# CR1000X_MUX.net
KiCad netlist of a schematic drawn in EAGLE
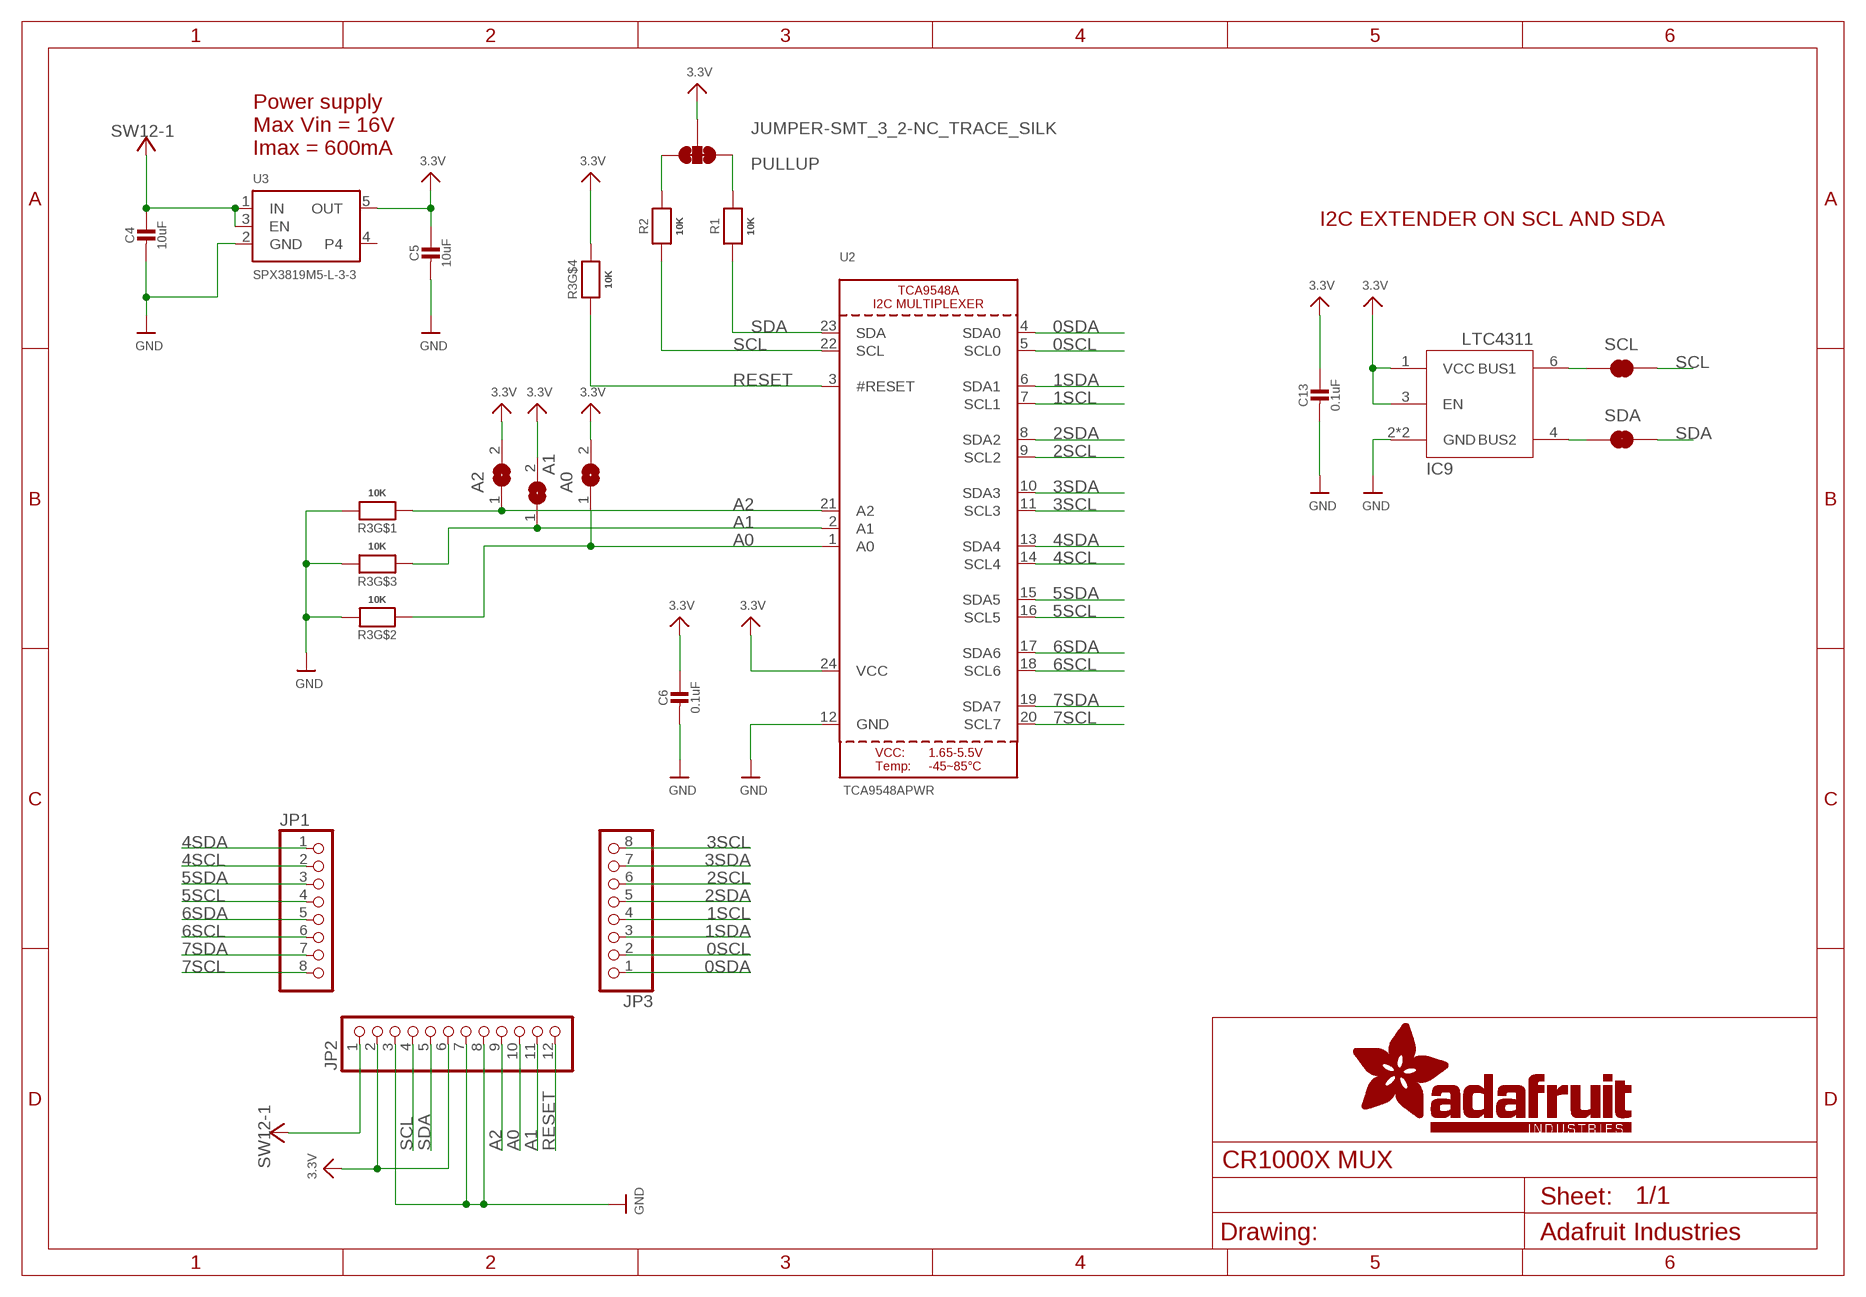
[diagram p0: schematic, sheet 1, part 1 of 2]
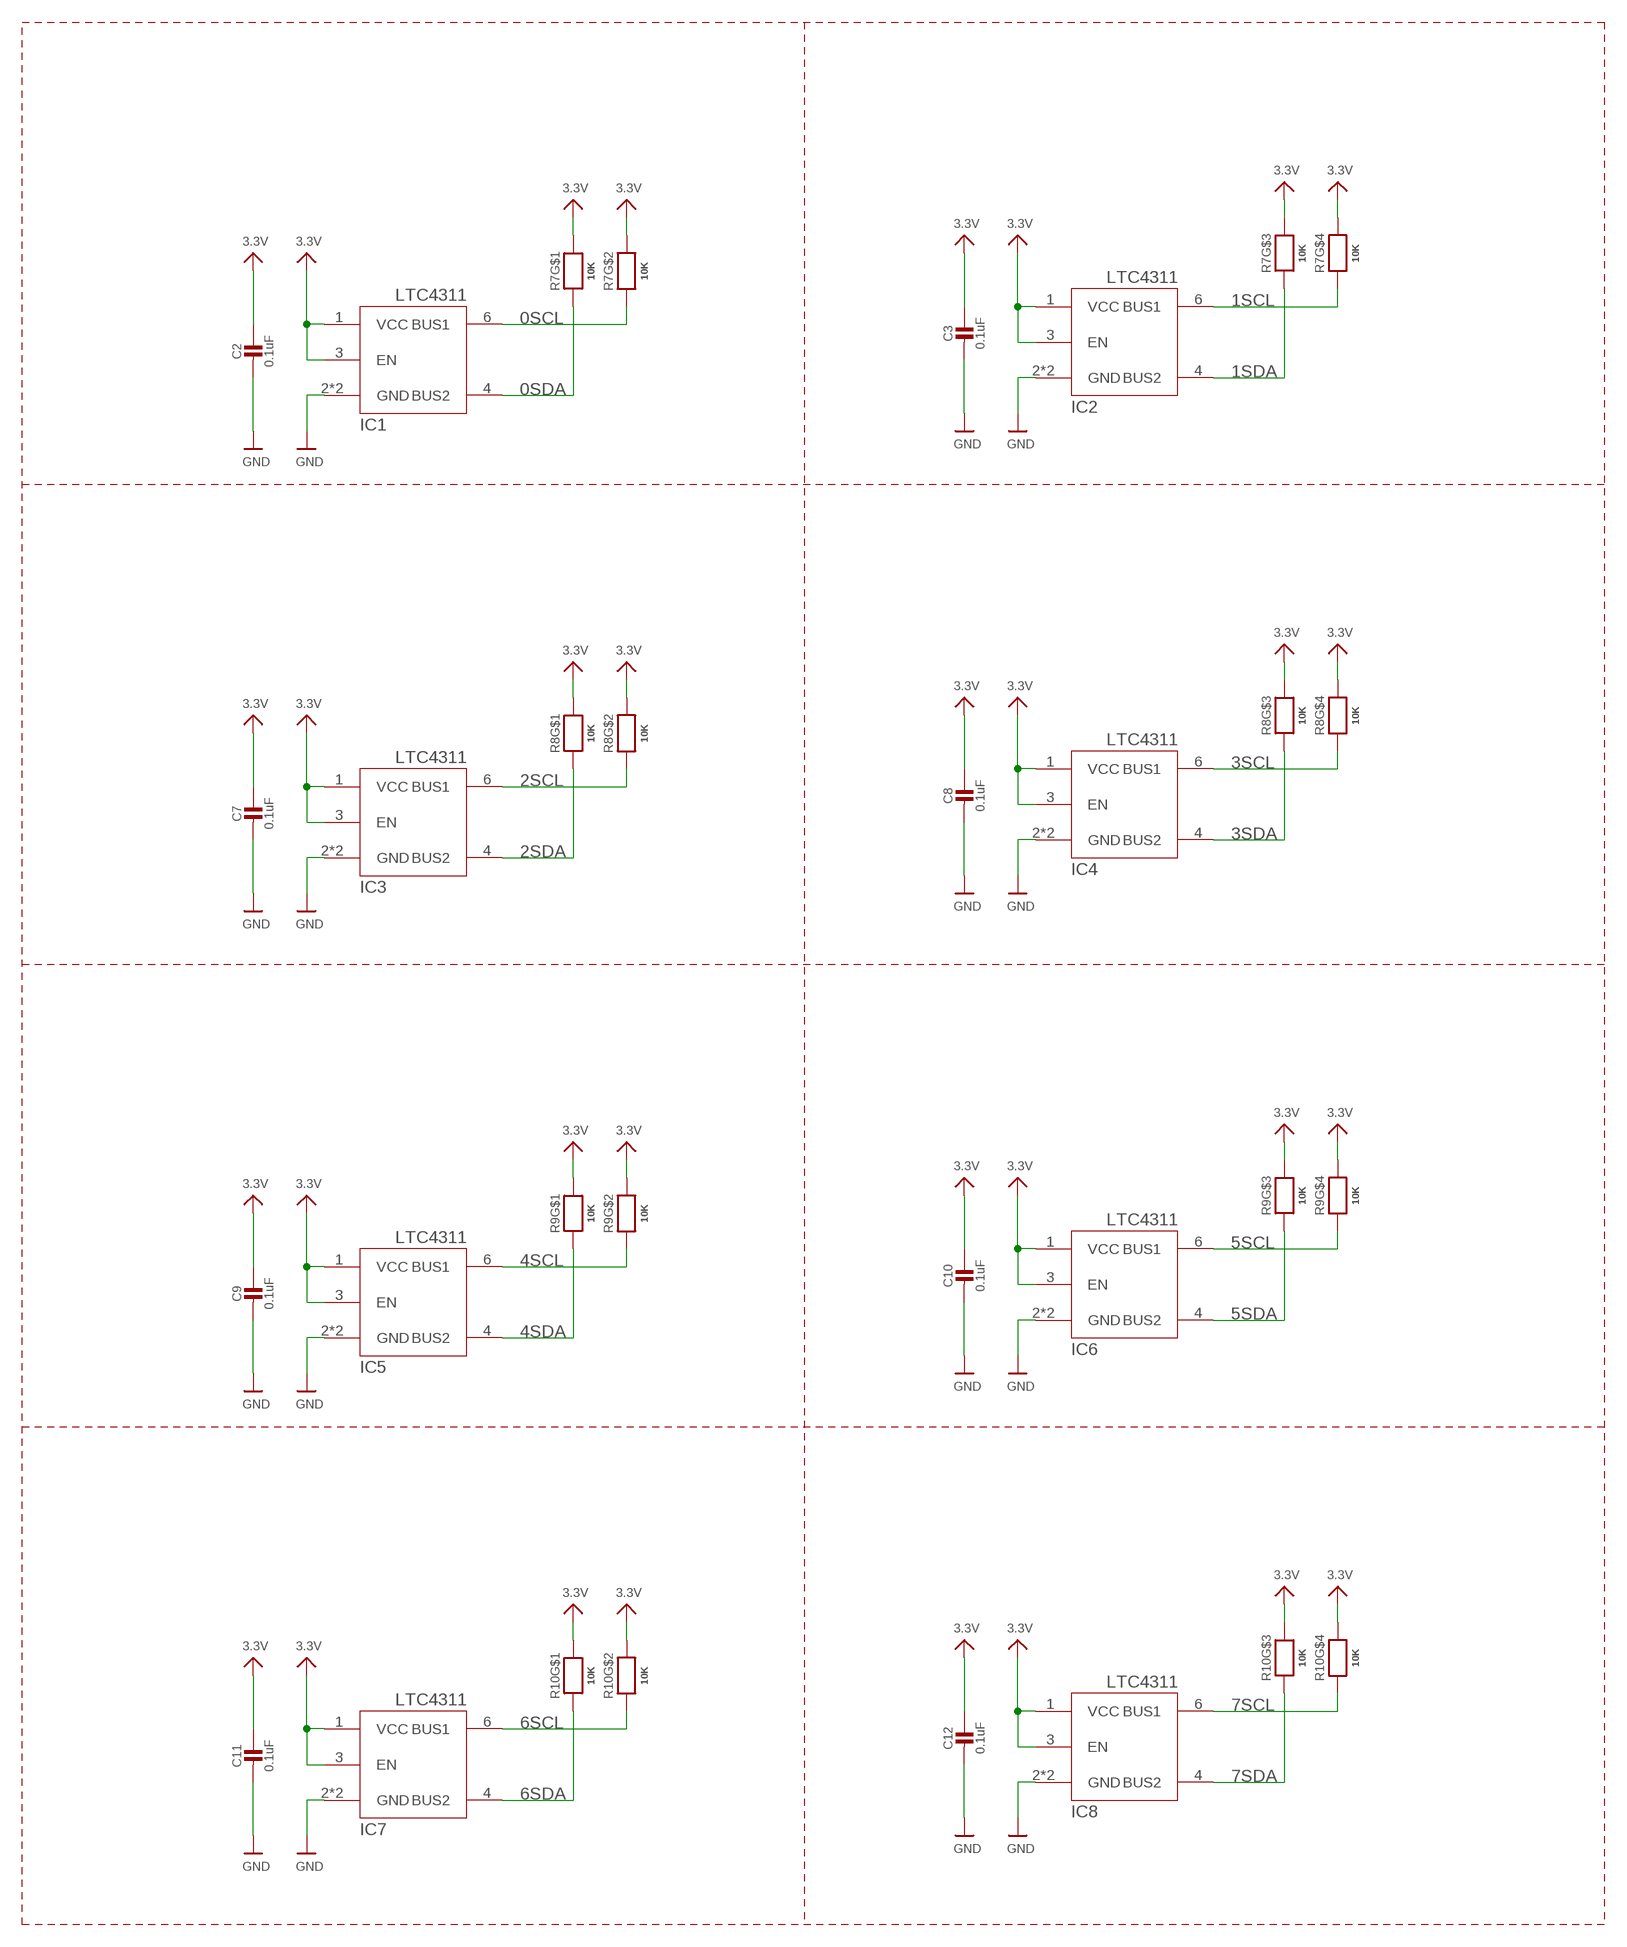
[diagram p1: schematic, sheet 1, part 2 of 2]

(export (version "E")
  (design (tool "Eeschema 10.0.6"))
  (components
    (comp (ref "A0")
      (value "SOLDERJUMPER")
      (footprint "eagle-import:SOLDERJUMPER_ARROW_NOPASTE")
      (libsource (lib "eagle-import") (part "SOLDERJUMPER"))
    )
    (comp (ref "A1")
      (value "SOLDERJUMPER")
      (footprint "eagle-import:SOLDERJUMPER_ARROW_NOPASTE")
      (libsource (lib "eagle-import") (part "SOLDERJUMPER"))
    )
    (comp (ref "A2")
      (value "SOLDERJUMPER")
      (footprint "eagle-import:SOLDERJUMPER_ARROW_NOPASTE")
      (libsource (lib "eagle-import") (part "SOLDERJUMPER"))
    )
    (comp (ref "C2")
      (value "0.1uF")
      (footprint "eagle-import:0603-NO")
      (libsource (lib "eagle-import") (part "CAP_CERAMIC0603_NO"))
    )
    (comp (ref "C3")
      (value "0.1uF")
      (footprint "eagle-import:0603-NO")
      (libsource (lib "eagle-import") (part "CAP_CERAMIC0603_NO"))
    )
    (comp (ref "C4")
      (value "10uF")
      (footprint "eagle-import:0805-NO")
      (libsource (lib "eagle-import") (part "CAP_CERAMIC0805-NOOUTLINE"))
    )
    (comp (ref "C5")
      (value "10uF")
      (footprint "eagle-import:0805-NO")
      (libsource (lib "eagle-import") (part "CAP_CERAMIC0805-NOOUTLINE"))
    )
    (comp (ref "C6")
      (value "0.1uF")
      (footprint "eagle-import:0603-NO")
      (libsource (lib "eagle-import") (part "CAP_CERAMIC0603_NO"))
    )
    (comp (ref "C7")
      (value "0.1uF")
      (footprint "eagle-import:0603-NO")
      (libsource (lib "eagle-import") (part "CAP_CERAMIC0603_NO"))
    )
    (comp (ref "C8")
      (value "0.1uF")
      (footprint "eagle-import:0603-NO")
      (libsource (lib "eagle-import") (part "CAP_CERAMIC0603_NO"))
    )
    (comp (ref "C9")
      (value "0.1uF")
      (footprint "eagle-import:0603-NO")
      (libsource (lib "eagle-import") (part "CAP_CERAMIC0603_NO"))
    )
    (comp (ref "C10")
      (value "0.1uF")
      (footprint "eagle-import:0603-NO")
      (libsource (lib "eagle-import") (part "CAP_CERAMIC0603_NO"))
    )
    (comp (ref "C11")
      (value "0.1uF")
      (footprint "eagle-import:0603-NO")
      (libsource (lib "eagle-import") (part "CAP_CERAMIC0603_NO"))
    )
    (comp (ref "C12")
      (value "0.1uF")
      (footprint "eagle-import:0603-NO")
      (libsource (lib "eagle-import") (part "CAP_CERAMIC0603_NO"))
    )
    (comp (ref "C13")
      (value "0.1uF")
      (footprint "eagle-import:0603-NO")
      (libsource (lib "eagle-import") (part "CAP_CERAMIC0603_NO"))
    )
    (comp (ref "IC1")
      (value "LTC4311_SC70")
      (footprint "eagle-import:SC70-6L")
      (libsource (lib "eagle-import") (part "LTC4311_SC70"))
    )
    (comp (ref "IC2")
      (value "LTC4311_SC70")
      (footprint "eagle-import:SC70-6L")
      (libsource (lib "eagle-import") (part "LTC4311_SC70"))
    )
    (comp (ref "IC3")
      (value "LTC4311_SC70")
      (footprint "eagle-import:SC70-6L")
      (libsource (lib "eagle-import") (part "LTC4311_SC70"))
    )
    (comp (ref "IC4")
      (value "LTC4311_SC70")
      (footprint "eagle-import:SC70-6L")
      (libsource (lib "eagle-import") (part "LTC4311_SC70"))
    )
    (comp (ref "IC5")
      (value "LTC4311_SC70")
      (footprint "eagle-import:SC70-6L")
      (libsource (lib "eagle-import") (part "LTC4311_SC70"))
    )
    (comp (ref "IC6")
      (value "LTC4311_SC70")
      (footprint "eagle-import:SC70-6L")
      (libsource (lib "eagle-import") (part "LTC4311_SC70"))
    )
    (comp (ref "IC7")
      (value "LTC4311_SC70")
      (footprint "eagle-import:SC70-6L")
      (libsource (lib "eagle-import") (part "LTC4311_SC70"))
    )
    (comp (ref "IC8")
      (value "LTC4311_SC70")
      (footprint "eagle-import:SC70-6L")
      (libsource (lib "eagle-import") (part "LTC4311_SC70"))
    )
    (comp (ref "IC9")
      (value "LTC4311_SC70")
      (footprint "eagle-import:SC70-6L")
      (libsource (lib "eagle-import") (part "LTC4311_SC70"))
    )
    (comp (ref "JP1")
      (value "PINHD-1X8BIG")
      (footprint "eagle-import:1X08-BIG")
      (libsource (lib "eagle-import") (part "PINHD-1X8BIG"))
    )
    (comp (ref "JP2")
      (value "HEADER-1X12")
      (footprint "eagle-import:1X12_ROUND")
      (libsource (lib "eagle-import") (part "HEADER-1X12"))
    )
    (comp (ref "JP3")
      (value "PINHD-1X8BIG")
      (footprint "eagle-import:1X08-BIG")
      (libsource (lib "eagle-import") (part "PINHD-1X8BIG"))
    )
    (comp (ref "PULLUP")
      (value "JUMPER-SMT_3_2-NC_TRACE_SILK")
      (footprint "eagle-import:SMT-JUMPER_3_2-NC_TRACE_SILK")
      (libsource (lib "eagle-import") (part "JUMPER-SMT_3_2-NC_TRACE_SILK"))
    )
    (comp (ref "R1")
      (value "10K")
      (footprint "eagle-import:0805-NO@1")
      (libsource (lib "eagle-import") (part "RESISTOR0805_NOOUTLINE"))
    )
    (comp (ref "R2")
      (value "10K")
      (footprint "eagle-import:0805-NO@1")
      (libsource (lib "eagle-import") (part "RESISTOR0805_NOOUTLINE"))
    )
    (comp (ref "R3")
      (value "10K")
      (footprint "eagle-import:RESPACK_4X0603")
      (libsource (lib "eagle-import") (part "RESISTOR_4PACK"))
    )
    (comp (ref "R7")
      (value "10K")
      (footprint "eagle-import:RESPACK_4X0603")
      (libsource (lib "eagle-import") (part "RESISTOR_4PACK"))
    )
    (comp (ref "R8")
      (value "10K")
      (footprint "eagle-import:RESPACK_4X0603")
      (libsource (lib "eagle-import") (part "RESISTOR_4PACK"))
    )
    (comp (ref "R9")
      (value "10K")
      (footprint "eagle-import:RESPACK_4X0603")
      (libsource (lib "eagle-import") (part "RESISTOR_4PACK"))
    )
    (comp (ref "R10")
      (value "10K")
      (footprint "eagle-import:RESPACK_4X0603")
      (libsource (lib "eagle-import") (part "RESISTOR_4PACK"))
    )
    (comp (ref "SCL")
      (value "JUMPER-SMT_2_NC_TRACE_SILK")
      (footprint "eagle-import:SMT-JUMPER_2_NC_TRACE_SILK")
      (libsource (lib "eagle-import") (part "JUMPER-SMT_2_NC_TRACE_SILK"))
    )
    (comp (ref "SDA")
      (value "JUMPER-SMT_2_NC_TRACE_SILK")
      (footprint "eagle-import:SMT-JUMPER_2_NC_TRACE_SILK")
      (libsource (lib "eagle-import") (part "JUMPER-SMT_2_NC_TRACE_SILK"))
    )
    (comp (ref "U2")
      (value "TCA9548APWR")
      (footprint "eagle-import:TSSOP24")
      (libsource (lib "eagle-import") (part "TCA9548A"))
    )
    (comp (ref "U3")
      (value "SPX3819M5-L-3-3")
      (footprint "eagle-import:SOT23-5")
      (libsource (lib "eagle-import") (part "VREG_SOT23-5"))
    )
  )
  (nets
    (net (code "1") (name "/0SCL") (class "Default")
      (node (ref "IC1") (pin "6") (pinfunction "BUS1_6") (pintype "bidirectional"))
      (node (ref "JP3") (pin "2") (pinfunction "2_2") (pintype "passive"))
      (node (ref "R7") (pin "7") (pinfunction "2_7") (pintype "passive"))
      (node (ref "U2") (pin "5") (pinfunction "SCL0_5") (pintype "bidirectional"))
    )
    (net (code "2") (name "/0SDA") (class "Default")
      (node (ref "IC1") (pin "4") (pinfunction "BUS2_4") (pintype "bidirectional"))
      (node (ref "JP3") (pin "1") (pinfunction "1_1") (pintype "passive"))
      (node (ref "R7") (pin "8") (pinfunction "2_8") (pintype "passive"))
      (node (ref "U2") (pin "4") (pinfunction "SDA0_4") (pintype "bidirectional"))
    )
    (net (code "3") (name "/1SCL") (class "Default")
      (node (ref "IC2") (pin "6") (pinfunction "BUS1_6") (pintype "bidirectional"))
      (node (ref "JP3") (pin "4") (pinfunction "4_4") (pintype "passive"))
      (node (ref "R7") (pin "5") (pinfunction "2_5") (pintype "passive"))
      (node (ref "U2") (pin "7") (pinfunction "SCL1_7") (pintype "bidirectional"))
    )
    (net (code "4") (name "/1SDA") (class "Default")
      (node (ref "IC2") (pin "4") (pinfunction "BUS2_4") (pintype "bidirectional"))
      (node (ref "JP3") (pin "3") (pinfunction "3_3") (pintype "passive"))
      (node (ref "R7") (pin "6") (pinfunction "2_6") (pintype "passive"))
      (node (ref "U2") (pin "6") (pinfunction "SDA1_6") (pintype "bidirectional"))
    )
    (net (code "5") (name "/2SCL") (class "Default")
      (node (ref "IC3") (pin "6") (pinfunction "BUS1_6") (pintype "bidirectional"))
      (node (ref "JP3") (pin "6") (pinfunction "6_6") (pintype "passive"))
      (node (ref "R8") (pin "7") (pinfunction "2_7") (pintype "passive"))
      (node (ref "U2") (pin "9") (pinfunction "SCL2_9") (pintype "bidirectional"))
    )
    (net (code "6") (name "/2SDA") (class "Default")
      (node (ref "IC3") (pin "4") (pinfunction "BUS2_4") (pintype "bidirectional"))
      (node (ref "JP3") (pin "5") (pinfunction "5_5") (pintype "passive"))
      (node (ref "R8") (pin "8") (pinfunction "2_8") (pintype "passive"))
      (node (ref "U2") (pin "8") (pinfunction "SDA2_8") (pintype "bidirectional"))
    )
    (net (code "7") (name "/3SCL") (class "Default")
      (node (ref "IC4") (pin "6") (pinfunction "BUS1_6") (pintype "bidirectional"))
      (node (ref "JP3") (pin "8") (pinfunction "8_8") (pintype "passive"))
      (node (ref "R8") (pin "5") (pinfunction "2_5") (pintype "passive"))
      (node (ref "U2") (pin "11") (pinfunction "SCL3_11") (pintype "bidirectional"))
    )
    (net (code "8") (name "/3SDA") (class "Default")
      (node (ref "IC4") (pin "4") (pinfunction "BUS2_4") (pintype "bidirectional"))
      (node (ref "JP3") (pin "7") (pinfunction "7_7") (pintype "passive"))
      (node (ref "R8") (pin "6") (pinfunction "2_6") (pintype "passive"))
      (node (ref "U2") (pin "10") (pinfunction "SDA3_10") (pintype "bidirectional"))
    )
    (net (code "9") (name "/4SCL") (class "Default")
      (node (ref "IC5") (pin "6") (pinfunction "BUS1_6") (pintype "bidirectional"))
      (node (ref "JP1") (pin "2") (pinfunction "2_2") (pintype "passive"))
      (node (ref "R9") (pin "7") (pinfunction "2_7") (pintype "passive"))
      (node (ref "U2") (pin "14") (pinfunction "SCL4_14") (pintype "bidirectional"))
    )
    (net (code "10") (name "/4SDA") (class "Default")
      (node (ref "IC5") (pin "4") (pinfunction "BUS2_4") (pintype "bidirectional"))
      (node (ref "JP1") (pin "1") (pinfunction "1_1") (pintype "passive"))
      (node (ref "R9") (pin "8") (pinfunction "2_8") (pintype "passive"))
      (node (ref "U2") (pin "13") (pinfunction "SDA4_13") (pintype "bidirectional"))
    )
    (net (code "11") (name "/5SCL") (class "Default")
      (node (ref "IC6") (pin "6") (pinfunction "BUS1_6") (pintype "bidirectional"))
      (node (ref "JP1") (pin "4") (pinfunction "4_4") (pintype "passive"))
      (node (ref "R9") (pin "5") (pinfunction "2_5") (pintype "passive"))
      (node (ref "U2") (pin "16") (pinfunction "SCL5_16") (pintype "bidirectional"))
    )
    (net (code "12") (name "/5SDA") (class "Default")
      (node (ref "IC6") (pin "4") (pinfunction "BUS2_4") (pintype "bidirectional"))
      (node (ref "JP1") (pin "3") (pinfunction "3_3") (pintype "passive"))
      (node (ref "R9") (pin "6") (pinfunction "2_6") (pintype "passive"))
      (node (ref "U2") (pin "15") (pinfunction "SDA5_15") (pintype "bidirectional"))
    )
    (net (code "13") (name "/6SCL") (class "Default")
      (node (ref "IC7") (pin "6") (pinfunction "BUS1_6") (pintype "bidirectional"))
      (node (ref "JP1") (pin "6") (pinfunction "6_6") (pintype "passive"))
      (node (ref "R10") (pin "7") (pinfunction "2_7") (pintype "passive"))
      (node (ref "U2") (pin "18") (pinfunction "SCL6_18") (pintype "bidirectional"))
    )
    (net (code "14") (name "/6SDA") (class "Default")
      (node (ref "IC7") (pin "4") (pinfunction "BUS2_4") (pintype "bidirectional"))
      (node (ref "JP1") (pin "5") (pinfunction "5_5") (pintype "passive"))
      (node (ref "R10") (pin "8") (pinfunction "2_8") (pintype "passive"))
      (node (ref "U2") (pin "17") (pinfunction "SDA6_17") (pintype "bidirectional"))
    )
    (net (code "15") (name "/7SCL") (class "Default")
      (node (ref "IC8") (pin "6") (pinfunction "BUS1_6") (pintype "bidirectional"))
      (node (ref "JP1") (pin "8") (pinfunction "8_8") (pintype "passive"))
      (node (ref "R10") (pin "5") (pinfunction "2_5") (pintype "passive"))
      (node (ref "U2") (pin "20") (pinfunction "SCL7_20") (pintype "bidirectional"))
    )
    (net (code "16") (name "/7SDA") (class "Default")
      (node (ref "IC8") (pin "4") (pinfunction "BUS2_4") (pintype "bidirectional"))
      (node (ref "JP1") (pin "7") (pinfunction "7_7") (pintype "passive"))
      (node (ref "R10") (pin "6") (pinfunction "2_6") (pintype "passive"))
      (node (ref "U2") (pin "19") (pinfunction "SDA7_19") (pintype "bidirectional"))
    )
    (net (code "17") (name "/A0") (class "Default")
      (node (ref "A0") (pin "1") (pinfunction "1_1") (pintype "passive"))
      (node (ref "JP2") (pin "10") (pinfunction "10_10") (pintype "passive"))
      (node (ref "R3") (pin "7") (pinfunction "2_7") (pintype "passive"))
      (node (ref "U2") (pin "1") (pinfunction "A0_1") (pintype "bidirectional"))
    )
    (net (code "18") (name "/A1") (class "Default")
      (node (ref "A1") (pin "1") (pinfunction "1_1") (pintype "passive"))
      (node (ref "JP2") (pin "11") (pinfunction "11_11") (pintype "passive"))
      (node (ref "R3") (pin "6") (pinfunction "2_6") (pintype "passive"))
      (node (ref "U2") (pin "2") (pinfunction "A1_2") (pintype "bidirectional"))
    )
    (net (code "19") (name "/A2") (class "Default")
      (node (ref "A2") (pin "1") (pinfunction "1_1") (pintype "passive"))
      (node (ref "JP2") (pin "9") (pinfunction "9_9") (pintype "passive"))
      (node (ref "R3") (pin "8") (pinfunction "2_8") (pintype "passive"))
      (node (ref "U2") (pin "21") (pinfunction "A2_21") (pintype "bidirectional"))
    )
    (net (code "20") (name "/RESET") (class "Default")
      (node (ref "JP2") (pin "12") (pinfunction "12_12") (pintype "passive"))
      (node (ref "R3") (pin "5") (pinfunction "2_5") (pintype "passive"))
      (node (ref "U2") (pin "3") (pinfunction "#RESET_3") (pintype "bidirectional"))
    )
    (net (code "21") (name "/SCL") (class "Default")
      (node (ref "JP2") (pin "4") (pinfunction "4_4") (pintype "passive"))
      (node (ref "R2") (pin "1") (pinfunction "1_1") (pintype "passive"))
      (node (ref "SCL") (pin "2") (pinfunction "2_2") (pintype "passive"))
      (node (ref "U2") (pin "22") (pinfunction "SCL_22") (pintype "bidirectional"))
    )
    (net (code "22") (name "/SDA") (class "Default")
      (node (ref "JP2") (pin "5") (pinfunction "5_5") (pintype "passive"))
      (node (ref "R1") (pin "1") (pinfunction "1_1") (pintype "passive"))
      (node (ref "SDA") (pin "2") (pinfunction "2_2") (pintype "passive"))
      (node (ref "U2") (pin "23") (pinfunction "SDA_23") (pintype "bidirectional"))
    )
    (net (code "23") (name "3.3V") (class "Default")
      (node (ref "A0") (pin "2") (pinfunction "2_2") (pintype "passive"))
      (node (ref "A1") (pin "2") (pinfunction "2_2") (pintype "passive"))
      (node (ref "A2") (pin "2") (pinfunction "2_2") (pintype "passive"))
      (node (ref "C10") (pin "1") (pinfunction "1_1") (pintype "passive"))
      (node (ref "C11") (pin "1") (pinfunction "1_1") (pintype "passive"))
      (node (ref "C12") (pin "1") (pinfunction "1_1") (pintype "passive"))
      (node (ref "C13") (pin "1") (pinfunction "1_1") (pintype "passive"))
      (node (ref "C2") (pin "1") (pinfunction "1_1") (pintype "passive"))
      (node (ref "C3") (pin "1") (pinfunction "1_1") (pintype "passive"))
      (node (ref "C5") (pin "1") (pinfunction "1_1") (pintype "passive"))
      (node (ref "C6") (pin "1") (pinfunction "1_1") (pintype "passive"))
      (node (ref "C7") (pin "1") (pinfunction "1_1") (pintype "passive"))
      (node (ref "C8") (pin "1") (pinfunction "1_1") (pintype "passive"))
      (node (ref "C9") (pin "1") (pinfunction "1_1") (pintype "passive"))
      (node (ref "IC1") (pin "1") (pinfunction "VCC_1") (pintype "power_in"))
      (node (ref "IC1") (pin "3") (pinfunction "EN_3") (pintype "input"))
      (node (ref "IC2") (pin "1") (pinfunction "VCC_1") (pintype "power_in"))
      (node (ref "IC2") (pin "3") (pinfunction "EN_3") (pintype "input"))
      (node (ref "IC3") (pin "1") (pinfunction "VCC_1") (pintype "power_in"))
      (node (ref "IC3") (pin "3") (pinfunction "EN_3") (pintype "input"))
      (node (ref "IC4") (pin "1") (pinfunction "VCC_1") (pintype "power_in"))
      (node (ref "IC4") (pin "3") (pinfunction "EN_3") (pintype "input"))
      (node (ref "IC5") (pin "1") (pinfunction "VCC_1") (pintype "power_in"))
      (node (ref "IC5") (pin "3") (pinfunction "EN_3") (pintype "input"))
      (node (ref "IC6") (pin "1") (pinfunction "VCC_1") (pintype "power_in"))
      (node (ref "IC6") (pin "3") (pinfunction "EN_3") (pintype "input"))
      (node (ref "IC7") (pin "1") (pinfunction "VCC_1") (pintype "power_in"))
      (node (ref "IC7") (pin "3") (pinfunction "EN_3") (pintype "input"))
      (node (ref "IC8") (pin "1") (pinfunction "VCC_1") (pintype "power_in"))
      (node (ref "IC8") (pin "3") (pinfunction "EN_3") (pintype "input"))
      (node (ref "IC9") (pin "1") (pinfunction "VCC_1") (pintype "power_in"))
      (node (ref "IC9") (pin "3") (pinfunction "EN_3") (pintype "input"))
      (node (ref "JP2") (pin "2") (pinfunction "2_2") (pintype "passive"))
      (node (ref "JP2") (pin "6") (pinfunction "6_6") (pintype "passive"))
      (node (ref "PULLUP") (pin "2") (pinfunction "2_2") (pintype "passive"))
      (node (ref "R10") (pin "1") (pinfunction "1_1") (pintype "passive"))
      (node (ref "R10") (pin "2") (pinfunction "1_2") (pintype "passive"))
      (node (ref "R10") (pin "3") (pinfunction "1_3") (pintype "passive"))
      (node (ref "R10") (pin "4") (pinfunction "1_4") (pintype "passive"))
      (node (ref "R3") (pin "4") (pinfunction "1_4") (pintype "passive"))
      (node (ref "R7") (pin "1") (pinfunction "1_1") (pintype "passive"))
      (node (ref "R7") (pin "2") (pinfunction "1_2") (pintype "passive"))
      (node (ref "R7") (pin "3") (pinfunction "1_3") (pintype "passive"))
      (node (ref "R7") (pin "4") (pinfunction "1_4") (pintype "passive"))
      (node (ref "R8") (pin "1") (pinfunction "1_1") (pintype "passive"))
      (node (ref "R8") (pin "2") (pinfunction "1_2") (pintype "passive"))
      (node (ref "R8") (pin "3") (pinfunction "1_3") (pintype "passive"))
      (node (ref "R8") (pin "4") (pinfunction "1_4") (pintype "passive"))
      (node (ref "R9") (pin "1") (pinfunction "1_1") (pintype "passive"))
      (node (ref "R9") (pin "2") (pinfunction "1_2") (pintype "passive"))
      (node (ref "R9") (pin "3") (pinfunction "1_3") (pintype "passive"))
      (node (ref "R9") (pin "4") (pinfunction "1_4") (pintype "passive"))
      (node (ref "U2") (pin "24") (pinfunction "VCC_24") (pintype "bidirectional"))
      (node (ref "U3") (pin "5") (pinfunction "OUT_5") (pintype "power_in"))
    )
    (net (code "24") (name "GND") (class "Default")
      (node (ref "C10") (pin "2") (pinfunction "2_2") (pintype "passive"))
      (node (ref "C11") (pin "2") (pinfunction "2_2") (pintype "passive"))
      (node (ref "C12") (pin "2") (pinfunction "2_2") (pintype "passive"))
      (node (ref "C13") (pin "2") (pinfunction "2_2") (pintype "passive"))
      (node (ref "C2") (pin "2") (pinfunction "2_2") (pintype "passive"))
      (node (ref "C3") (pin "2") (pinfunction "2_2") (pintype "passive"))
      (node (ref "C4") (pin "2") (pinfunction "2_2") (pintype "passive"))
      (node (ref "C5") (pin "2") (pinfunction "2_2") (pintype "passive"))
      (node (ref "C6") (pin "2") (pinfunction "2_2") (pintype "passive"))
      (node (ref "C7") (pin "2") (pinfunction "2_2") (pintype "passive"))
      (node (ref "C8") (pin "2") (pinfunction "2_2") (pintype "passive"))
      (node (ref "C9") (pin "2") (pinfunction "2_2") (pintype "passive"))
      (node (ref "IC1") (pin "2") (pinfunction "GND_2") (pintype "power_in"))
      (node (ref "IC1") (pin "5") (pinfunction "GND_5") (pintype "power_in"))
      (node (ref "IC2") (pin "2") (pinfunction "GND_2") (pintype "power_in"))
      (node (ref "IC2") (pin "5") (pinfunction "GND_5") (pintype "power_in"))
      (node (ref "IC3") (pin "2") (pinfunction "GND_2") (pintype "power_in"))
      (node (ref "IC3") (pin "5") (pinfunction "GND_5") (pintype "power_in"))
      (node (ref "IC4") (pin "2") (pinfunction "GND_2") (pintype "power_in"))
      (node (ref "IC4") (pin "5") (pinfunction "GND_5") (pintype "power_in"))
      (node (ref "IC5") (pin "2") (pinfunction "GND_2") (pintype "power_in"))
      (node (ref "IC5") (pin "5") (pinfunction "GND_5") (pintype "power_in"))
      (node (ref "IC6") (pin "2") (pinfunction "GND_2") (pintype "power_in"))
      (node (ref "IC6") (pin "5") (pinfunction "GND_5") (pintype "power_in"))
      (node (ref "IC7") (pin "2") (pinfunction "GND_2") (pintype "power_in"))
      (node (ref "IC7") (pin "5") (pinfunction "GND_5") (pintype "power_in"))
      (node (ref "IC8") (pin "2") (pinfunction "GND_2") (pintype "power_in"))
      (node (ref "IC8") (pin "5") (pinfunction "GND_5") (pintype "power_in"))
      (node (ref "IC9") (pin "2") (pinfunction "GND_2") (pintype "power_in"))
      (node (ref "IC9") (pin "5") (pinfunction "GND_5") (pintype "power_in"))
      (node (ref "JP2") (pin "3") (pinfunction "3_3") (pintype "passive"))
      (node (ref "JP2") (pin "7") (pinfunction "7_7") (pintype "passive"))
      (node (ref "JP2") (pin "8") (pinfunction "8_8") (pintype "passive"))
      (node (ref "R3") (pin "1") (pinfunction "1_1") (pintype "passive"))
      (node (ref "R3") (pin "2") (pinfunction "1_2") (pintype "passive"))
      (node (ref "R3") (pin "3") (pinfunction "1_3") (pintype "passive"))
      (node (ref "U2") (pin "12") (pinfunction "GND_12") (pintype "bidirectional"))
      (node (ref "U3") (pin "2") (pinfunction "GND_2") (pintype "power_in"))
    )
    (net (code "25") (name "Net-(IC9-BUS1)") (class "Default")
      (node (ref "IC9") (pin "6") (pinfunction "BUS1_6") (pintype "bidirectional"))
      (node (ref "SCL") (pin "1") (pinfunction "1_1") (pintype "passive"))
    )
    (net (code "26") (name "Net-(IC9-BUS2)") (class "Default")
      (node (ref "IC9") (pin "4") (pinfunction "BUS2_4") (pintype "bidirectional"))
      (node (ref "SDA") (pin "1") (pinfunction "1_1") (pintype "passive"))
    )
    (net (code "27") (name "Net-(PULLUP-Pad1)") (class "Default")
      (node (ref "PULLUP") (pin "1") (pinfunction "1_1") (pintype "passive"))
      (node (ref "R1") (pin "2") (pinfunction "2_2") (pintype "passive"))
    )
    (net (code "28") (name "Net-(PULLUP-Pad3)") (class "Default")
      (node (ref "PULLUP") (pin "3") (pinfunction "3_3") (pintype "passive"))
      (node (ref "R2") (pin "2") (pinfunction "2_2") (pintype "passive"))
    )
    (net (code "29") (name "SW12-1") (class "Default")
      (node (ref "C4") (pin "1") (pinfunction "1_1") (pintype "passive"))
      (node (ref "JP2") (pin "1") (pinfunction "1_1") (pintype "passive"))
      (node (ref "U3") (pin "1") (pinfunction "IN_1") (pintype "power_in"))
      (node (ref "U3") (pin "3") (pinfunction "EN_3") (pintype "input"))
    )
    (net (code "30") (name "unconnected-(U3-P4-Pad4)") (class "Default")
      (node (ref "U3") (pin "4") (pinfunction "P4_4") (pintype "bidirectional"))
    )
  )
)
